# Supply.net
KiCad netlist of a schematic drawn in Altium Designer
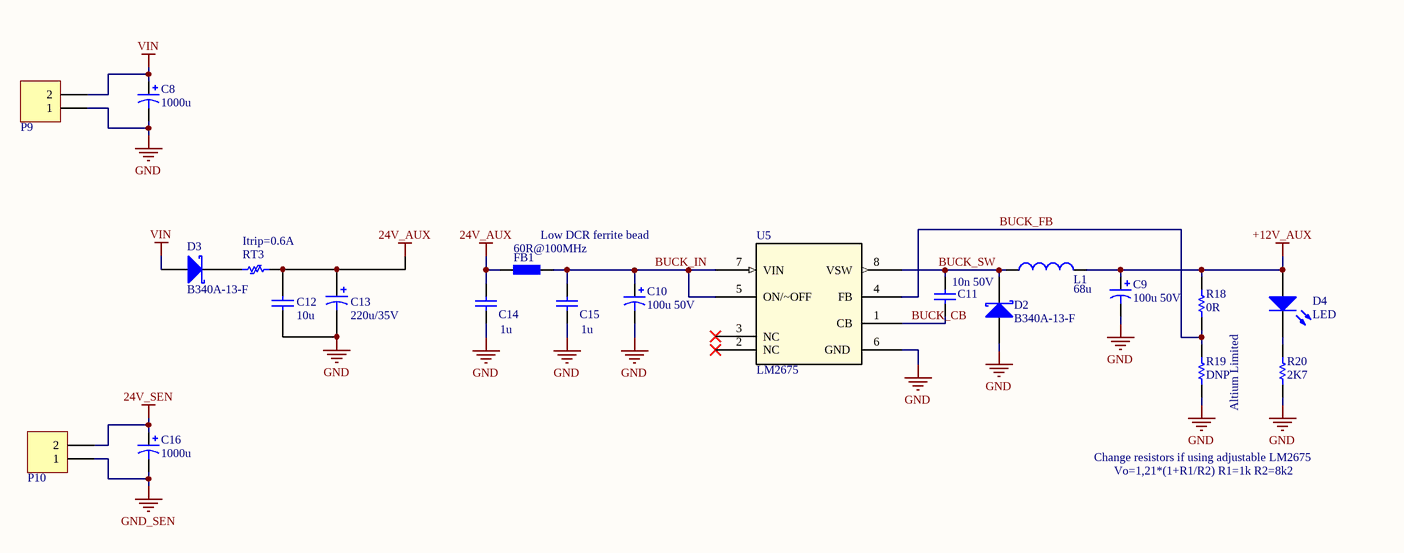
[diagram p0: Supply.SchDoc]

(export (version "E")
  (design (tool "Eeschema 10.0.6"))
  (components
    (comp (ref "C8")
      (value "1000u")
      (footprint "CAP_P10MM-D22MM")
      (description "Polarized Capacitor (Axial)")
      (fields (field (name "Comment") "Cap Pol2") (field (name "PUBLISHER") "Altium Limited"))
      (libsource (lib "Misc") (part "Cap Pol2"))
    )
    (comp (ref "C9")
      (value "100u 50V")
      (footprint "FKV Panasonic 6.3x7.7L (D8)")
      (description "Polarized Capacitor (Axial)")
      (fields (field (name "Comment") "Cap Pol2") (field (name "PUBLISHER") "Altium Limited"))
      (libsource (lib "Misc") (part "Cap Pol2"))
    )
    (comp (ref "C10")
      (value "100u 50V")
      (footprint "FKV Panasonic 6.3x7.7L (D8)")
      (description "Polarized Capacitor (Axial)")
      (fields (field (name "Comment") "Cap Pol2") (field (name "PUBLISHER") "Altium Limited"))
      (libsource (lib "Misc") (part "Cap Pol2"))
    )
    (comp (ref "C11")
      (value "10n 50V")
      (footprint "SMD_CAP_0805")
      (description "Capacitor")
      (fields (field (name "PUBLISHER") "Altium Limited"))
      (libsource (lib "Misc") (part "Capacitor"))
    )
    (comp (ref "C12")
      (value "10u")
      (footprint "SMT1210_M")
      (description "Capacitor")
      (fields (field (name "Comment") "X7R/1210/50V") (field (name "PUBLISHER") "Altium Limited"))
      (libsource (lib "Miscellaneous Devices") (part "Cap"))
    )
    (comp (ref "C13")
      (value "220u/35V")
      (footprint "FKV Panasonic 8x10.2L (F)")
      (description "Polarized Capacitor (Radial)")
      (fields (field (name "Comment") "8x10.2"))
      (libsource (lib "Miscellaneous Devices") (part "Cap Pol1"))
    )
    (comp (ref "C14")
      (value "1u")
      (footprint "SMT0805_M")
      (description "Capacitor")
      (fields (field (name "PUBLISHER") "Altium Limited"))
      (libsource (lib "Misc") (part "Capacitor"))
    )
    (comp (ref "C15")
      (value "1u")
      (footprint "SMT0805_M")
      (description "Capacitor")
      (fields (field (name "PUBLISHER") "Altium Limited"))
      (libsource (lib "Misc") (part "Capacitor"))
    )
    (comp (ref "C16")
      (value "1000u")
      (footprint "CAP_P10MM-D22MM")
      (description "Polarized Capacitor (Axial)")
      (fields (field (name "Comment") "Cap Pol2") (field (name "PUBLISHER") "Altium Limited"))
      (libsource (lib "Misc") (part "Cap Pol2"))
    )
    (comp (ref "D2")
      (value "B340A-13-F")
      (footprint "SMB")
      (description "Schottky Diode")
      (libsource (lib "Miscellaneous Devices") (part "D Schottky"))
    )
    (comp (ref "D3")
      (value "B340A-13-F")
      (footprint "SMB")
      (description "Schottky Diode")
      (libsource (lib "Miscellaneous Devices") (part "D Schottky"))
    )
    (comp (ref "D4")
      (value "LED")
      (footprint "LED-3mm")
      (description "Typical INFRARED GaAs LED")
      (fields (field (name "PUBLISHER") "Altium Limited"))
      (libsource (lib "Misc") (part "LED"))
    )
    (comp (ref "FB1")
      (value "60R@100MHz")
      (footprint "SMT0805_M")
      (libsource (lib "Misc") (part "Ferrite Bead"))
    )
    (comp (ref "L1")
      (value "68u")
      (footprint "IND MSS1278 COILCRAFT")
      (fields (field (name "Comment") "Inductor"))
      (libsource (lib "Misc") (part "Inductor"))
    )
    (comp (ref "P9")
      (value "ECH350V-02P")
      (footprint "ECH350V-02P")
      (libsource (lib "Connectors") (part "ECH350V-02P"))
    )
    (comp (ref "P10")
      (value "ECH350V-02P")
      (footprint "ECH350V-02P")
      (libsource (lib "Connectors") (part "ECH350V-02P"))
    )
    (comp (ref "R18")
      (value "0R")
      (footprint "SMD_RES_0805")
      (description "Resistor")
      (fields (field (name "Comment") "Res") (field (name "PUBLISHER") "Altium Limited"))
      (libsource (lib "Misc") (part "Res"))
    )
    (comp (ref "R19")
      (value "DNP")
      (footprint "SMD_RES_0805")
      (description "Resistor")
      (fields (field (name "PUBLISHER") "Altium Limited") (field (name "Comment") "Res"))
      (libsource (lib "Misc") (part "Res"))
    )
    (comp (ref "R20")
      (value "2K7")
      (footprint "SMT0805_M")
      (description "Resistor")
      (fields (field (name "Comment") "Res") (field (name "PUBLISHER") "Altium Limited"))
      (libsource (lib "Misc") (part "Res"))
    )
    (comp (ref "RT3")
      (value "Itrip=0.6A")
      (footprint "AXIAL-0.2")
      (description "Thermistor")
      (fields (field (name "PUBLISHER") "Altium Limited"))
      (libsource (lib "Misc") (part "Poly Switch"))
    )
    (comp (ref "U5")
      (value "LM2675")
      (footprint "SOIC-8-M")
      (description "SIMPLE SWITCHER&reg; 6.5V to 40V, 1A Low Component Count Step-Down Regulator 8-SOIC -40 to 125")
      (fields
        (field (name "MANUFACTURER_PART_NUMBER") "LM2675M-12")
        (field (name "COPYRIGHT") "Copyright (C) 2025 Ultra Librarian. All rights reserved.")
      )
      (libsource (lib "Supply") (part "LM2675"))
    )
  )
  (nets
    (net (code "1") (name "+12V_AUX") (class "Default")
      (node (ref "C9") (pin "1") (pinfunction "1_1") (pintype "passive"))
      (node (ref "D4") (pin "1") (pinfunction "A_1") (pintype "passive"))
      (node (ref "L1") (pin "2") (pinfunction "2_2") (pintype "passive"))
      (node (ref "R18") (pin "1") (pinfunction "1_1") (pintype "passive"))
    )
    (net (code "2") (name "/BUCK_CB") (class "Default")
      (node (ref "C11") (pin "1") (pinfunction "1_1") (pintype "passive"))
      (node (ref "U5") (pin "1") (pinfunction "CB_1") (pintype "passive"))
    )
    (net (code "3") (name "/BUCK_FB") (class "Default")
      (node (ref "R18") (pin "2") (pinfunction "2_2") (pintype "passive"))
      (node (ref "R19") (pin "1") (pinfunction "1_1") (pintype "passive"))
      (node (ref "U5") (pin "4") (pinfunction "FB_4") (pintype "passive"))
    )
    (net (code "4") (name "/BUCK_IN") (class "Default")
      (node (ref "C10") (pin "1") (pinfunction "1_1") (pintype "passive"))
      (node (ref "C15") (pin "2") (pinfunction "2_2") (pintype "passive"))
      (node (ref "FB1") (pin "2") (pinfunction "2_2") (pintype "passive"))
      (node (ref "U5") (pin "5") (pinfunction "ON/~OFF_5") (pintype "passive"))
      (node (ref "U5") (pin "7") (pinfunction "VIN_7") (pintype "input"))
    )
    (net (code "5") (name "/BUCK_SW") (class "Default")
      (node (ref "C11") (pin "2") (pinfunction "2_2") (pintype "passive"))
      (node (ref "D2") (pin "2") (pinfunction "K_2") (pintype "passive"))
      (node (ref "L1") (pin "1") (pinfunction "1_1") (pintype "passive"))
      (node (ref "U5") (pin "8") (pinfunction "VSW_8") (pintype "output"))
    )
    (net (code "6") (name "24V_AUX") (class "Default")
      (node (ref "C12") (pin "2") (pinfunction "2_2") (pintype "passive"))
      (node (ref "C13") (pin "1") (pinfunction "1_1") (pintype "passive"))
      (node (ref "C14") (pin "2") (pinfunction "2_2") (pintype "passive"))
      (node (ref "FB1") (pin "1") (pinfunction "1_1") (pintype "passive"))
      (node (ref "RT3") (pin "1") (pinfunction "1_1") (pintype "passive"))
    )
    (net (code "7") (name "24V_SEN") (class "Default")
      (node (ref "C16") (pin "1") (pinfunction "1_1") (pintype "passive"))
      (node (ref "P10") (pin "2") (pinfunction "2_2") (pintype "passive"))
    )
    (net (code "8") (name "GND") (class "Default")
      (node (ref "C10") (pin "2") (pinfunction "2_2") (pintype "passive"))
      (node (ref "C12") (pin "1") (pinfunction "1_1") (pintype "passive"))
      (node (ref "C13") (pin "2") (pinfunction "2_2") (pintype "passive"))
      (node (ref "C14") (pin "1") (pinfunction "1_1") (pintype "passive"))
      (node (ref "C15") (pin "1") (pinfunction "1_1") (pintype "passive"))
      (node (ref "C8") (pin "2") (pinfunction "2_2") (pintype "passive"))
      (node (ref "C9") (pin "2") (pinfunction "2_2") (pintype "passive"))
      (node (ref "D2") (pin "1") (pinfunction "A_1") (pintype "passive"))
      (node (ref "P9") (pin "1") (pinfunction "1_1") (pintype "passive"))
      (node (ref "R19") (pin "2") (pinfunction "2_2") (pintype "passive"))
      (node (ref "R20") (pin "1") (pinfunction "1_1") (pintype "passive"))
      (node (ref "U5") (pin "6") (pinfunction "GND_6") (pintype "passive"))
    )
    (net (code "9") (name "GND_SEN") (class "Default")
      (node (ref "C16") (pin "2") (pinfunction "2_2") (pintype "passive"))
      (node (ref "P10") (pin "1") (pinfunction "1_1") (pintype "passive"))
    )
    (net (code "10") (name "Net-(D3-K)") (class "Default")
      (node (ref "D3") (pin "2") (pinfunction "K_2") (pintype "passive"))
      (node (ref "RT3") (pin "2") (pinfunction "2_2") (pintype "passive"))
    )
    (net (code "11") (name "Net-(D4-K)") (class "Default")
      (node (ref "D4") (pin "2") (pinfunction "K_2") (pintype "passive"))
      (node (ref "R20") (pin "2") (pinfunction "2_2") (pintype "passive"))
    )
    (net (code "12") (name "VIN") (class "Default")
      (node (ref "C8") (pin "1") (pinfunction "1_1") (pintype "passive"))
      (node (ref "D3") (pin "1") (pinfunction "A_1") (pintype "passive"))
      (node (ref "P9") (pin "2") (pinfunction "2_2") (pintype "passive"))
    )
    (net (code "13") (name "unconnected-(U5-NC-Pad2)") (class "Default")
      (node (ref "U5") (pin "2") (pinfunction "NC_2") (pintype "passive+no_connect"))
    )
    (net (code "14") (name "unconnected-(U5-NC-Pad3)") (class "Default")
      (node (ref "U5") (pin "3") (pinfunction "NC_3") (pintype "passive+no_connect"))
    )
  )
)
